# controller-buttons.net
KiCad netlist of a schematic drawn in EAGLE
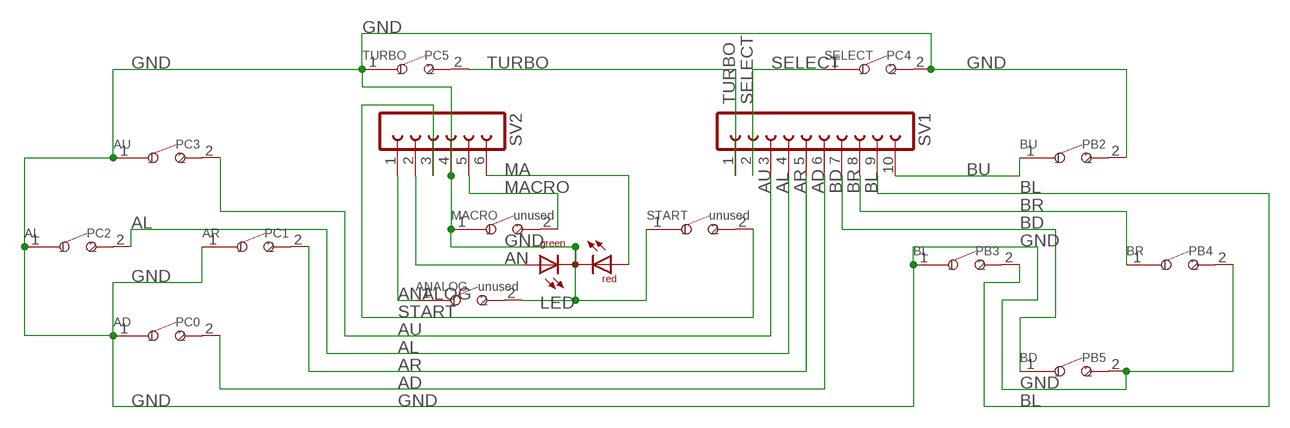
[diagram p0: schematic, sheet 1]

(export (version "E")
  (design (tool "Eeschema 10.0.6"))
  (components
    (comp (ref "AD")
      (value "PC0")
      (footprint "eagle-import:SW2-5.0-6.0X3.0X4.3MM")
      (fields (field (name "MPN") "TS-1101F"))
      (libsource (lib "eagle-import") (part "DIP-BUTTON(2P-6.0X3.0X4.3MM)-TS-1101F"))
    )
    (comp (ref "AL")
      (value "PC2")
      (footprint "eagle-import:SW2-5.0-6.0X3.0X4.3MM")
      (fields (field (name "MPN") "TS-1101F"))
      (libsource (lib "eagle-import") (part "DIP-BUTTON(2P-6.0X3.0X4.3MM)-TS-1101F"))
    )
    (comp (ref "ANALOG")
      (value "unused")
      (footprint "eagle-import:SW2-5.0-6.0X3.0X4.3MM")
      (fields (field (name "MPN") "TS-1101F"))
      (libsource (lib "eagle-import") (part "DIP-BUTTON(2P-6.0X3.0X4.3MM)-TS-1101F"))
    )
    (comp (ref "AR")
      (value "PC1")
      (footprint "eagle-import:SW2-5.0-6.0X3.0X4.3MM")
      (fields (field (name "MPN") "TS-1101F"))
      (libsource (lib "eagle-import") (part "DIP-BUTTON(2P-6.0X3.0X4.3MM)-TS-1101F"))
    )
    (comp (ref "AU")
      (value "PC3")
      (footprint "eagle-import:SW2-5.0-6.0X3.0X4.3MM")
      (fields (field (name "MPN") "TS-1101F"))
      (libsource (lib "eagle-import") (part "DIP-BUTTON(2P-6.0X3.0X4.3MM)-TS-1101F"))
    )
    (comp (ref "BD")
      (value "PB5")
      (footprint "eagle-import:SW2-5.0-6.0X3.0X4.3MM")
      (fields (field (name "MPN") "TS-1101F"))
      (libsource (lib "eagle-import") (part "DIP-BUTTON(2P-6.0X3.0X4.3MM)-TS-1101F"))
    )
    (comp (ref "BL")
      (value "PB3")
      (footprint "eagle-import:SW2-5.0-6.0X3.0X4.3MM")
      (fields (field (name "MPN") "TS-1101F"))
      (libsource (lib "eagle-import") (part "DIP-BUTTON(2P-6.0X3.0X4.3MM)-TS-1101F"))
    )
    (comp (ref "BR")
      (value "PB4")
      (footprint "eagle-import:SW2-5.0-6.0X3.0X4.3MM")
      (fields (field (name "MPN") "TS-1101F"))
      (libsource (lib "eagle-import") (part "DIP-BUTTON(2P-6.0X3.0X4.3MM)-TS-1101F"))
    )
    (comp (ref "BU")
      (value "PB2")
      (footprint "eagle-import:SW2-5.0-6.0X3.0X4.3MM")
      (fields (field (name "MPN") "TS-1101F"))
      (libsource (lib "eagle-import") (part "DIP-BUTTON(2P-6.0X3.0X4.3MM)-TS-1101F"))
    )
    (comp (ref "LED")
      (value "DUOLED-RG-C")
      (footprint "eagle-import:DUOLED-C-5MM")
      (libsource (lib "eagle-import") (part "DUOLED-RG-C"))
    )
    (comp (ref "MACRO")
      (value "unused")
      (footprint "eagle-import:SW2-5.0-6.0X3.0X4.3MM")
      (fields (field (name "MPN") "TS-1101F"))
      (libsource (lib "eagle-import") (part "DIP-BUTTON(2P-6.0X3.0X4.3MM)-TS-1101F"))
    )
    (comp (ref "SELECT")
      (value "PC4")
      (footprint "eagle-import:SW2-5.0-6.0X3.0X4.3MM")
      (fields (field (name "MPN") "TS-1101F"))
      (libsource (lib "eagle-import") (part "DIP-BUTTON(2P-6.0X3.0X4.3MM)-TS-1101F"))
    )
    (comp (ref "START")
      (value "unused")
      (footprint "eagle-import:SW2-5.0-6.0X3.0X4.3MM")
      (fields (field (name "MPN") "TS-1101F"))
      (libsource (lib "eagle-import") (part "DIP-BUTTON(2P-6.0X3.0X4.3MM)-TS-1101F"))
    )
    (comp (ref "SV1")
      (value "FE10-1")
      (footprint "eagle-import:FE10")
      (libsource (lib "eagle-import") (part "FE10-1"))
    )
    (comp (ref "SV2")
      (value "FE06-1")
      (footprint "eagle-import:FE06")
      (libsource (lib "eagle-import") (part "FE06-1"))
    )
    (comp (ref "TURBO")
      (value "PC5")
      (footprint "eagle-import:SW2-5.0-6.0X3.0X4.3MM")
      (fields (field (name "MPN") "TS-1101F"))
      (libsource (lib "eagle-import") (part "DIP-BUTTON(2P-6.0X3.0X4.3MM)-TS-1101F"))
    )
  )
  (nets
    (net (code "1") (name "/AD") (class "Default")
      (node (ref "AD") (pin "2") (pinfunction "2_2") (pintype "bidirectional"))
      (node (ref "SV1") (pin "6") (pinfunction "6_6") (pintype "passive"))
    )
    (net (code "2") (name "/AL") (class "Default")
      (node (ref "AL") (pin "2") (pinfunction "2_2") (pintype "bidirectional"))
      (node (ref "SV1") (pin "4") (pinfunction "4_4") (pintype "passive"))
    )
    (net (code "3") (name "/AN") (class "Default")
      (node (ref "LED") (pin "AX") (pinfunction "AG_AX") (pintype "passive"))
      (node (ref "SV2") (pin "2") (pinfunction "2_2") (pintype "passive"))
    )
    (net (code "4") (name "/ANALOG") (class "Default")
      (node (ref "ANALOG") (pin "1") (pinfunction "1_1") (pintype "bidirectional"))
      (node (ref "SV2") (pin "1") (pinfunction "1_1") (pintype "passive"))
    )
    (net (code "5") (name "/AR") (class "Default")
      (node (ref "AR") (pin "2") (pinfunction "2_2") (pintype "bidirectional"))
      (node (ref "SV1") (pin "5") (pinfunction "5_5") (pintype "passive"))
    )
    (net (code "6") (name "/AU") (class "Default")
      (node (ref "AU") (pin "2") (pinfunction "2_2") (pintype "bidirectional"))
      (node (ref "SV1") (pin "3") (pinfunction "3_3") (pintype "passive"))
    )
    (net (code "7") (name "/BD") (class "Default")
      (node (ref "BD") (pin "1") (pinfunction "1_1") (pintype "bidirectional"))
      (node (ref "SV1") (pin "7") (pinfunction "7_7") (pintype "passive"))
    )
    (net (code "8") (name "/BL") (class "Default")
      (node (ref "BL") (pin "2") (pinfunction "2_2") (pintype "bidirectional"))
      (node (ref "SV1") (pin "9") (pinfunction "9_9") (pintype "passive"))
    )
    (net (code "9") (name "/BR") (class "Default")
      (node (ref "BR") (pin "1") (pinfunction "1_1") (pintype "bidirectional"))
      (node (ref "SV1") (pin "8") (pinfunction "8_8") (pintype "passive"))
    )
    (net (code "10") (name "/BU") (class "Default")
      (node (ref "BU") (pin "1") (pinfunction "1_1") (pintype "bidirectional"))
      (node (ref "SV1") (pin "10") (pinfunction "10_10") (pintype "passive"))
    )
    (net (code "11") (name "/GND") (class "Default")
      (node (ref "AD") (pin "1") (pinfunction "1_1") (pintype "bidirectional"))
      (node (ref "AL") (pin "1") (pinfunction "1_1") (pintype "bidirectional"))
      (node (ref "ANALOG") (pin "2") (pinfunction "2_2") (pintype "bidirectional"))
      (node (ref "AR") (pin "1") (pinfunction "1_1") (pintype "bidirectional"))
      (node (ref "AU") (pin "1") (pinfunction "1_1") (pintype "bidirectional"))
      (node (ref "BD") (pin "2") (pinfunction "2_2") (pintype "bidirectional"))
      (node (ref "BL") (pin "1") (pinfunction "1_1") (pintype "bidirectional"))
      (node (ref "BR") (pin "2") (pinfunction "2_2") (pintype "bidirectional"))
      (node (ref "BU") (pin "2") (pinfunction "2_2") (pintype "bidirectional"))
      (node (ref "LED") (pin "C") (pinfunction "C_C") (pintype "passive"))
      (node (ref "MACRO") (pin "1") (pinfunction "1_1") (pintype "bidirectional"))
      (node (ref "SELECT") (pin "2") (pinfunction "2_2") (pintype "bidirectional"))
      (node (ref "START") (pin "1") (pinfunction "1_1") (pintype "bidirectional"))
      (node (ref "SV2") (pin "4") (pinfunction "4_4") (pintype "passive"))
      (node (ref "TURBO") (pin "1") (pinfunction "1_1") (pintype "bidirectional"))
    )
    (net (code "12") (name "/MA") (class "Default")
      (node (ref "LED") (pin "AR") (pinfunction "AR_AR") (pintype "passive"))
      (node (ref "SV2") (pin "6") (pinfunction "6_6") (pintype "passive"))
    )
    (net (code "13") (name "/MACRO") (class "Default")
      (node (ref "MACRO") (pin "2") (pinfunction "2_2") (pintype "bidirectional"))
      (node (ref "SV2") (pin "5") (pinfunction "5_5") (pintype "passive"))
    )
    (net (code "14") (name "/SELECT") (class "Default")
      (node (ref "SELECT") (pin "1") (pinfunction "1_1") (pintype "bidirectional"))
      (node (ref "SV1") (pin "2") (pinfunction "2_2") (pintype "passive"))
    )
    (net (code "15") (name "/START") (class "Default")
      (node (ref "START") (pin "2") (pinfunction "2_2") (pintype "bidirectional"))
      (node (ref "SV2") (pin "3") (pinfunction "3_3") (pintype "passive"))
    )
    (net (code "16") (name "/TURBO") (class "Default")
      (node (ref "SV1") (pin "1") (pinfunction "1_1") (pintype "passive"))
      (node (ref "TURBO") (pin "2") (pinfunction "2_2") (pintype "bidirectional"))
    )
  )
)
